# untitled.net
KiCad netlist of a schematic drawn in EAGLE
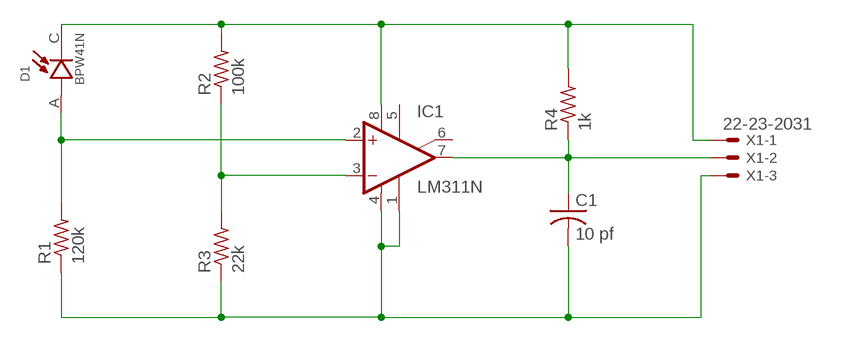
[diagram p0: schematic, sheet 1]

(export (version "E")
  (design (tool "Eeschema 10.0.6"))
  (components
    (comp (ref "C1")
      (value "10 pf")
      (footprint "eagle-import:C025-024X044")
      (libsource (lib "eagle-import") (part "C-US025-024X044"))
    )
    (comp (ref "D1")
      (value "BPW41N")
      (footprint "eagle-import:DIO_BPW41N")
      (fields (field (name "MF") "Vishay Semiconductor Opto Division"))
      (libsource (lib "eagle-import") (part "BPW41N"))
    )
    (comp (ref "IC1")
      (value "LM311N")
      (footprint "eagle-import:DIL08")
      (libsource (lib "eagle-import") (part "LM311N"))
    )
    (comp (ref "R1")
      (value "120k")
      (footprint "eagle-import:0204_5")
      (libsource (lib "eagle-import") (part "R-US_0204/5"))
    )
    (comp (ref "R2")
      (value "100k")
      (footprint "eagle-import:0204_5")
      (libsource (lib "eagle-import") (part "R-US_0204/5"))
    )
    (comp (ref "R3")
      (value "22k")
      (footprint "eagle-import:0204_5")
      (libsource (lib "eagle-import") (part "R-US_0204/5"))
    )
    (comp (ref "R4")
      (value "1k")
      (footprint "eagle-import:0204_5")
      (libsource (lib "eagle-import") (part "R-US_0204/5"))
    )
    (comp (ref "X1")
      (value "22-23-2031")
      (footprint "eagle-import:22-23-2031")
      (fields (field (name "MF") "MOLEX"))
      (libsource (lib "eagle-import") (part "22-23-2031"))
    )
  )
  (nets
    (net (code "1") (name "Net-(IC1-+IN)") (class "Default")
      (node (ref "D1") (pin "A") (pinfunction "A_A") (pintype "passive"))
      (node (ref "IC1") (pin "2") (pinfunction "+IN_2") (pintype "input"))
      (node (ref "R1") (pin "2") (pinfunction "2_2") (pintype "passive"))
    )
    (net (code "2") (name "Net-(IC1--IN)") (class "Default")
      (node (ref "IC1") (pin "3") (pinfunction "-IN_3") (pintype "input"))
      (node (ref "R2") (pin "1") (pinfunction "1_1") (pintype "passive"))
      (node (ref "R3") (pin "2") (pinfunction "2_2") (pintype "passive"))
    )
    (net (code "3") (name "Net-(IC1-GND)") (class "Default")
      (node (ref "C1") (pin "2") (pinfunction "2_2") (pintype "passive"))
      (node (ref "IC1") (pin "1") (pinfunction "GND_1") (pintype "passive"))
      (node (ref "IC1") (pin "4") (pinfunction "V-_4") (pintype "power_in"))
      (node (ref "R1") (pin "1") (pinfunction "1_1") (pintype "passive"))
      (node (ref "R3") (pin "1") (pinfunction "1_1") (pintype "passive"))
      (node (ref "X1") (pin "3") (pinfunction "S_3") (pintype "passive"))
    )
    (net (code "4") (name "Net-(IC1-OUT)") (class "Default")
      (node (ref "C1") (pin "1") (pinfunction "1_1") (pintype "passive"))
      (node (ref "IC1") (pin "7") (pinfunction "OUT_7") (pintype "output"))
      (node (ref "R4") (pin "1") (pinfunction "1_1") (pintype "passive"))
      (node (ref "X1") (pin "2") (pinfunction "S_2") (pintype "passive"))
    )
    (net (code "5") (name "Net-(IC1-V+)") (class "Default")
      (node (ref "D1") (pin "C") (pinfunction "C_C") (pintype "passive"))
      (node (ref "IC1") (pin "8") (pinfunction "V+_8") (pintype "power_in"))
      (node (ref "R2") (pin "2") (pinfunction "2_2") (pintype "passive"))
      (node (ref "R4") (pin "2") (pinfunction "2_2") (pintype "passive"))
      (node (ref "X1") (pin "1") (pinfunction "S_1") (pintype "passive"))
    )
    (net (code "6") (name "unconnected-(IC1-ON-Pad5)") (class "Default")
      (node (ref "IC1") (pin "5") (pinfunction "ON_5") (pintype "passive"))
    )
    (net (code "7") (name "unconnected-(IC1-ON{slash}STR-Pad6)") (class "Default")
      (node (ref "IC1") (pin "6") (pinfunction "ON/STR_6") (pintype "passive"))
    )
  )
)
